# angularclock.net
KiCad netlist of a schematic drawn in EAGLE
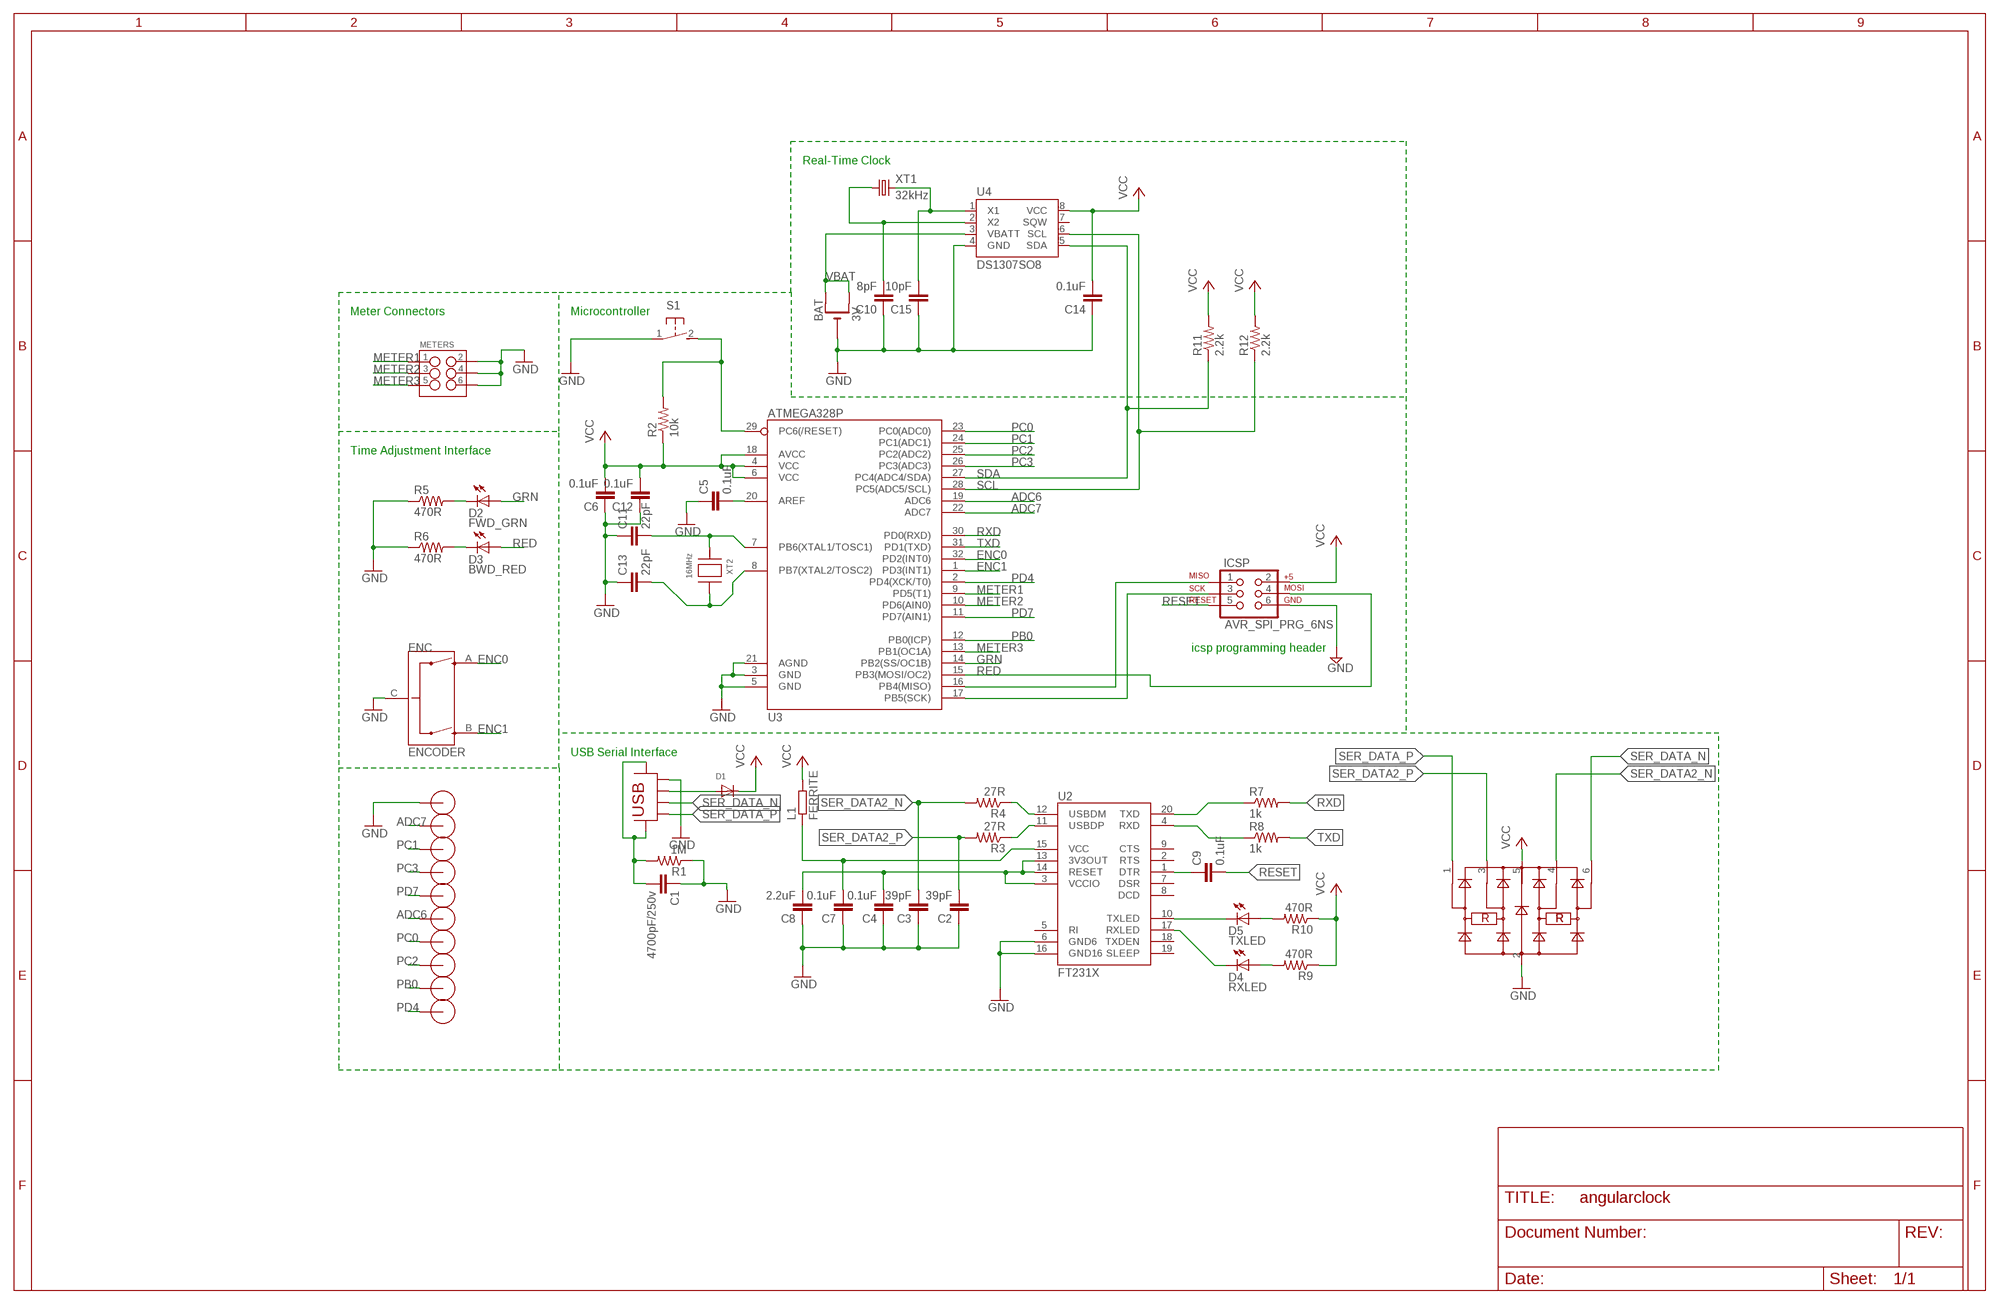
[diagram p0: schematic, sheet 1]

(export (version "E")
  (design (tool "Eeschema 10.0.6"))
  (components
    (comp (ref "BAT")
      (value "3V")
      (footprint "eagle-import:CR1220-THM")
      (libsource (lib "eagle-import") (part "CR1220THM"))
    )
    (comp (ref "C1")
      (value "4700pF/250v")
      (footprint "eagle-import:0805")
      (libsource (lib "eagle-import") (part "CAP0805"))
    )
    (comp (ref "C2")
      (value "39pF")
      (footprint "eagle-import:0805")
      (libsource (lib "eagle-import") (part "CAP0805"))
    )
    (comp (ref "C3")
      (value "39pF")
      (footprint "eagle-import:0805")
      (libsource (lib "eagle-import") (part "CAP0805"))
    )
    (comp (ref "C4")
      (value "0.1uF")
      (footprint "eagle-import:0805")
      (libsource (lib "eagle-import") (part "CAP0805"))
    )
    (comp (ref "C5")
      (value "0.1uF")
      (footprint "eagle-import:0805")
      (libsource (lib "eagle-import") (part "CAP0805"))
    )
    (comp (ref "C6")
      (value "0.1uF")
      (footprint "eagle-import:0805")
      (libsource (lib "eagle-import") (part "CAP0805"))
    )
    (comp (ref "C7")
      (value "0.1uF")
      (footprint "eagle-import:0805")
      (libsource (lib "eagle-import") (part "CAP0805"))
    )
    (comp (ref "C8")
      (value "2.2uF")
      (footprint "eagle-import:0805")
      (libsource (lib "eagle-import") (part "CAP0805"))
    )
    (comp (ref "C9")
      (value "0.1uF")
      (footprint "eagle-import:0805")
      (libsource (lib "eagle-import") (part "CAP0805"))
    )
    (comp (ref "C10")
      (value "8pF")
      (footprint "eagle-import:0805")
      (libsource (lib "eagle-import") (part "CAP0805"))
    )
    (comp (ref "C11")
      (value "22pF")
      (footprint "eagle-import:0805")
      (libsource (lib "eagle-import") (part "CAP0805"))
    )
    (comp (ref "C12")
      (value "0.1uF")
      (footprint "eagle-import:0805")
      (libsource (lib "eagle-import") (part "CAP0805"))
    )
    (comp (ref "C13")
      (value "22pF")
      (footprint "eagle-import:0805")
      (libsource (lib "eagle-import") (part "CAP0805"))
    )
    (comp (ref "C14")
      (value "0.1uF")
      (footprint "eagle-import:0805")
      (libsource (lib "eagle-import") (part "CAP0805"))
    )
    (comp (ref "C15")
      (value "10pF")
      (footprint "eagle-import:0805")
      (libsource (lib "eagle-import") (part "CAP0805"))
    )
    (comp (ref "D1")
      (value "MBRM130LT1G")
      (footprint "eagle-import:DO-216AA")
      (libsource (lib "eagle-import") (part "MBRM130LT1G"))
    )
    (comp (ref "D2")
      (value "FWD_GRN")
      (footprint "eagle-import:CHIPLED_0805")
      (libsource (lib "eagle-import") (part "LEDCHIPLED_0805"))
    )
    (comp (ref "D3")
      (value "BWD_RED")
      (footprint "eagle-import:CHIPLED_0805")
      (libsource (lib "eagle-import") (part "LEDCHIPLED_0805"))
    )
    (comp (ref "D4")
      (value "RXLED")
      (footprint "eagle-import:CHIPLED_0805")
      (libsource (lib "eagle-import") (part "LEDCHIPLED_0805"))
    )
    (comp (ref "D5")
      (value "TXLED")
      (footprint "eagle-import:CHIPLED_0805")
      (libsource (lib "eagle-import") (part "LEDCHIPLED_0805"))
    )
    (comp (ref "ENC")
      (value "ENCODER")
      (footprint "eagle-import:ENCODER-16MM-QUAD")
      (libsource (lib "eagle-import") (part "ENCODER-QUADRATURE"))
    )
    (comp (ref "ICSP")
      (value "AVR_SPI_PRG_6NS")
      (footprint "eagle-import:2X3-NS")
      (libsource (lib "eagle-import") (part "AVR_SPI_PRG_6NS"))
    )
    (comp (ref "L1")
      (value "FERRITE")
      (footprint "eagle-import:R0805")
      (libsource (lib "eagle-import") (part "R-EU_R0805"))
    )
    (comp (ref "METERS")
      (value "M03X2NO_SILK")
      (footprint "eagle-import:2X3-NS")
      (libsource (lib "eagle-import") (part "M03X2NO_SILK"))
    )
    (comp (ref "R1")
      (value "1M")
      (footprint "eagle-import:0805")
      (libsource (lib "eagle-import") (part "RESISTOR0805-RES"))
    )
    (comp (ref "R2")
      (value "10k")
      (footprint "eagle-import:0805")
      (libsource (lib "eagle-import") (part "RESISTOR0805-RES"))
    )
    (comp (ref "R3")
      (value "27R")
      (footprint "eagle-import:0805")
      (libsource (lib "eagle-import") (part "RESISTOR0805-RES"))
    )
    (comp (ref "R4")
      (value "27R")
      (footprint "eagle-import:0805")
      (libsource (lib "eagle-import") (part "RESISTOR0805-RES"))
    )
    (comp (ref "R5")
      (value "470R")
      (footprint "eagle-import:0805")
      (libsource (lib "eagle-import") (part "RESISTOR0805-RES"))
    )
    (comp (ref "R6")
      (value "470R")
      (footprint "eagle-import:0805")
      (libsource (lib "eagle-import") (part "RESISTOR0805-RES"))
    )
    (comp (ref "R7")
      (value "1k")
      (footprint "eagle-import:0805")
      (libsource (lib "eagle-import") (part "RESISTOR0805-RES"))
    )
    (comp (ref "R8")
      (value "1k")
      (footprint "eagle-import:0805")
      (libsource (lib "eagle-import") (part "RESISTOR0805-RES"))
    )
    (comp (ref "R9")
      (value "470R")
      (footprint "eagle-import:0805")
      (libsource (lib "eagle-import") (part "RESISTOR0805-RES"))
    )
    (comp (ref "R10")
      (value "470R")
      (footprint "eagle-import:0805")
      (libsource (lib "eagle-import") (part "RESISTOR0805-RES"))
    )
    (comp (ref "R11")
      (value "2.2k")
      (footprint "eagle-import:0805")
      (libsource (lib "eagle-import") (part "RESISTOR0805-RES"))
    )
    (comp (ref "R12")
      (value "2.2k")
      (footprint "eagle-import:0805")
      (libsource (lib "eagle-import") (part "RESISTOR0805-RES"))
    )
    (comp (ref "S1")
      (value "31-XX")
      (footprint "eagle-import:B3F-31XX")
      (libsource (lib "eagle-import") (part "31-XX"))
    )
    (comp (ref "U$1")
      (value "1PIN")
      (footprint "eagle-import:1PIN")
      (libsource (lib "eagle-import") (part "1PIN"))
    )
    (comp (ref "U$2")
      (value "1PIN")
      (footprint "eagle-import:1PIN")
      (libsource (lib "eagle-import") (part "1PIN"))
    )
    (comp (ref "U$3")
      (value "1PIN")
      (footprint "eagle-import:1PIN")
      (libsource (lib "eagle-import") (part "1PIN"))
    )
    (comp (ref "U$4")
      (value "1PIN")
      (footprint "eagle-import:1PIN")
      (libsource (lib "eagle-import") (part "1PIN"))
    )
    (comp (ref "U$5")
      (value "1PIN")
      (footprint "eagle-import:1PIN")
      (libsource (lib "eagle-import") (part "1PIN"))
    )
    (comp (ref "U$6")
      (value "1PIN")
      (footprint "eagle-import:1PIN")
      (libsource (lib "eagle-import") (part "1PIN"))
    )
    (comp (ref "U$7")
      (value "1PIN")
      (footprint "eagle-import:1PIN")
      (libsource (lib "eagle-import") (part "1PIN"))
    )
    (comp (ref "U$8")
      (value "1PIN")
      (footprint "eagle-import:1PIN")
      (libsource (lib "eagle-import") (part "1PIN"))
    )
    (comp (ref "U$9")
      (value "1PIN")
      (footprint "eagle-import:1PIN")
      (libsource (lib "eagle-import") (part "1PIN"))
    )
    (comp (ref "U$10")
      (value "1PIN")
      (footprint "eagle-import:1PIN")
      (libsource (lib "eagle-import") (part "1PIN"))
    )
    (comp (ref "U1")
      (value "IP4234CZ6")
      (footprint "eagle-import:SOT457")
      (libsource (lib "eagle-import") (part "IP4234CZ6"))
    )
    (comp (ref "U2")
      (value "FT231X")
      (footprint "eagle-import:SSOP20")
      (libsource (lib "eagle-import") (part "FT231X"))
    )
    (comp (ref "U3")
      (value "ATMEGA328P")
      (footprint "eagle-import:TQFP32-08")
      (libsource (lib "eagle-import") (part "ATMEGA328_SMT"))
    )
    (comp (ref "U4")
      (value "DS1307SO8")
      (footprint "eagle-import:SO08")
      (libsource (lib "eagle-import") (part "DS1307SO8"))
    )
    (comp (ref "USB")
      (value "MICRO-USB-POWERMICRO-USB-2-ROUND-HOLES")
      (footprint "eagle-import:WICKED-DEVICE_MICRO-USB-4")
      (libsource (lib "eagle-import") (part "WICKED-DEVICE_MICRO-USB-POWERMICRO-USB-4"))
    )
    (comp (ref "XT1")
      (value "32kHz")
      (footprint "eagle-import:CRYSTAL_TC26V")
      (libsource (lib "eagle-import") (part "CRYSTAL_CRYSTALTC26V"))
    )
    (comp (ref "XT2")
      (value "16MHz")
      (footprint "eagle-import:ABLS")
      (libsource (lib "eagle-import") (part "ABLS"))
    )
  )
  (nets
    (net (code "1") (name "/ADC6") (class "Default")
      (node (ref "U$1") (pin "1") (pinfunction "1_1") (pintype "bidirectional"))
      (node (ref "U3") (pin "19") (pinfunction "ADC6_19") (pintype "bidirectional"))
    )
    (net (code "2") (name "/ADC7") (class "Default")
      (node (ref "U$4") (pin "1") (pinfunction "1_1") (pintype "bidirectional"))
      (node (ref "U3") (pin "22") (pinfunction "ADC7_22") (pintype "bidirectional"))
    )
    (net (code "3") (name "/ENC0") (class "Default")
      (node (ref "ENC") (pin "A") (pinfunction "A_A") (pintype "bidirectional"))
      (node (ref "U3") (pin "32") (pinfunction "PD2(INT0)_32") (pintype "bidirectional"))
    )
    (net (code "4") (name "/ENC1") (class "Default")
      (node (ref "ENC") (pin "B") (pinfunction "B_B") (pintype "bidirectional"))
      (node (ref "U3") (pin "1") (pinfunction "PD3(INT1)_1") (pintype "bidirectional"))
    )
    (net (code "5") (name "/GRN") (class "Default")
      (node (ref "D2") (pin "A") (pinfunction "A_A") (pintype "passive"))
      (node (ref "U3") (pin "14") (pinfunction "PB2(SS/OC1B)_14") (pintype "bidirectional"))
    )
    (net (code "6") (name "/METER1") (class "Default")
      (node (ref "METERS") (pin "1") (pinfunction "1_1") (pintype "bidirectional"))
      (node (ref "U3") (pin "9") (pinfunction "PD5(T1)_9") (pintype "bidirectional"))
    )
    (net (code "7") (name "/METER2") (class "Default")
      (node (ref "METERS") (pin "3") (pinfunction "3_3") (pintype "bidirectional"))
      (node (ref "U3") (pin "10") (pinfunction "PD6(AIN0)_10") (pintype "bidirectional"))
    )
    (net (code "8") (name "/METER3") (class "Default")
      (node (ref "METERS") (pin "5") (pinfunction "5_5") (pintype "bidirectional"))
      (node (ref "U3") (pin "13") (pinfunction "PB1(OC1A)_13") (pintype "bidirectional"))
    )
    (net (code "9") (name "/PB0") (class "Default")
      (node (ref "U$5") (pin "1") (pinfunction "1_1") (pintype "bidirectional"))
      (node (ref "U3") (pin "12") (pinfunction "PB0(ICP)_12") (pintype "bidirectional"))
    )
    (net (code "10") (name "/PC0") (class "Default")
      (node (ref "U$3") (pin "1") (pinfunction "1_1") (pintype "bidirectional"))
      (node (ref "U3") (pin "23") (pinfunction "PC0(ADC0)_23") (pintype "bidirectional"))
    )
    (net (code "11") (name "/PC1") (class "Default")
      (node (ref "U$6") (pin "1") (pinfunction "1_1") (pintype "bidirectional"))
      (node (ref "U3") (pin "24") (pinfunction "PC1(ADC1)_24") (pintype "bidirectional"))
    )
    (net (code "12") (name "/PC2") (class "Default")
      (node (ref "U$7") (pin "1") (pinfunction "1_1") (pintype "bidirectional"))
      (node (ref "U3") (pin "25") (pinfunction "PC2(ADC2)_25") (pintype "bidirectional"))
    )
    (net (code "13") (name "/PC3") (class "Default")
      (node (ref "U$10") (pin "1") (pinfunction "1_1") (pintype "bidirectional"))
      (node (ref "U3") (pin "26") (pinfunction "PC3(ADC3)_26") (pintype "bidirectional"))
    )
    (net (code "14") (name "/PD4") (class "Default")
      (node (ref "U$9") (pin "1") (pinfunction "1_1") (pintype "bidirectional"))
      (node (ref "U3") (pin "2") (pinfunction "PD4(XCK/T0)_2") (pintype "bidirectional"))
    )
    (net (code "15") (name "/PD7") (class "Default")
      (node (ref "U$8") (pin "1") (pinfunction "1_1") (pintype "bidirectional"))
      (node (ref "U3") (pin "11") (pinfunction "PD7(AIN1)_11") (pintype "bidirectional"))
    )
    (net (code "16") (name "/RED") (class "Default")
      (node (ref "D3") (pin "A") (pinfunction "A_A") (pintype "passive"))
      (node (ref "ICSP") (pin "4") (pinfunction "4_4") (pintype "passive"))
      (node (ref "U3") (pin "15") (pinfunction "PB3(MOSI/OC2)_15") (pintype "bidirectional"))
    )
    (net (code "17") (name "/SCL") (class "Default")
      (node (ref "R12") (pin "1") (pinfunction "1_1") (pintype "passive"))
      (node (ref "U3") (pin "28") (pinfunction "PC5(ADC5/SCL)_28") (pintype "bidirectional"))
      (node (ref "U4") (pin "6") (pinfunction "SCL_6") (pintype "bidirectional"))
    )
    (net (code "18") (name "/SDA") (class "Default")
      (node (ref "R11") (pin "1") (pinfunction "1_1") (pintype "passive"))
      (node (ref "U3") (pin "27") (pinfunction "PC4(ADC4/SDA)_27") (pintype "bidirectional"))
      (node (ref "U4") (pin "5") (pinfunction "SDA_5") (pintype "bidirectional"))
    )
    (net (code "19") (name "/VBAT") (class "Default")
      (node (ref "BAT") (pin "+1") (pinfunction "+_+1") (pintype "passive"))
      (node (ref "BAT") (pin "+2") (pinfunction "+1_+2") (pintype "passive"))
      (node (ref "U4") (pin "3") (pinfunction "VBATT_3") (pintype "bidirectional"))
    )
    (net (code "20") (name "GND") (class "Default")
      (node (ref "BAT") (pin "-") (pinfunction "-_-") (pintype "passive"))
      (node (ref "C1") (pin "1") (pinfunction "1_1") (pintype "passive"))
      (node (ref "C10") (pin "1") (pinfunction "1_1") (pintype "passive"))
      (node (ref "C11") (pin "1") (pinfunction "1_1") (pintype "passive"))
      (node (ref "C12") (pin "1") (pinfunction "1_1") (pintype "passive"))
      (node (ref "C13") (pin "1") (pinfunction "1_1") (pintype "passive"))
      (node (ref "C14") (pin "1") (pinfunction "1_1") (pintype "passive"))
      (node (ref "C15") (pin "1") (pinfunction "1_1") (pintype "passive"))
      (node (ref "C2") (pin "1") (pinfunction "1_1") (pintype "passive"))
      (node (ref "C3") (pin "1") (pinfunction "1_1") (pintype "passive"))
      (node (ref "C4") (pin "1") (pinfunction "1_1") (pintype "passive"))
      (node (ref "C5") (pin "1") (pinfunction "1_1") (pintype "passive"))
      (node (ref "C6") (pin "1") (pinfunction "1_1") (pintype "passive"))
      (node (ref "C7") (pin "1") (pinfunction "1_1") (pintype "passive"))
      (node (ref "C8") (pin "1") (pinfunction "1_1") (pintype "passive"))
      (node (ref "ENC") (pin "C") (pinfunction "C_C") (pintype "bidirectional"))
      (node (ref "ICSP") (pin "6") (pinfunction "6_6") (pintype "passive"))
      (node (ref "METERS") (pin "2") (pinfunction "2_2") (pintype "bidirectional"))
      (node (ref "METERS") (pin "4") (pinfunction "4_4") (pintype "bidirectional"))
      (node (ref "METERS") (pin "6") (pinfunction "6_6") (pintype "bidirectional"))
      (node (ref "R1") (pin "1") (pinfunction "1_1") (pintype "passive"))
      (node (ref "R5") (pin "1") (pinfunction "1_1") (pintype "passive"))
      (node (ref "R6") (pin "1") (pinfunction "1_1") (pintype "passive"))
      (node (ref "S1") (pin "1") (pinfunction "P_1") (pintype "passive"))
      (node (ref "U$2") (pin "1") (pinfunction "1_1") (pintype "bidirectional"))
      (node (ref "U1") (pin "2") (pinfunction "2_2") (pintype "bidirectional"))
      (node (ref "U2") (pin "16") (pinfunction "GND16_16") (pintype "power_in"))
      (node (ref "U2") (pin "6") (pinfunction "GND6_6") (pintype "power_in"))
      (node (ref "U3") (pin "21") (pinfunction "AGND_21") (pintype "bidirectional"))
      (node (ref "U3") (pin "3") (pinfunction "GND_3") (pintype "bidirectional"))
      (node (ref "U3") (pin "5") (pinfunction "GND_5") (pintype "bidirectional"))
      (node (ref "U4") (pin "4") (pinfunction "GND_4") (pintype "bidirectional"))
      (node (ref "USB") (pin "GND") (pinfunction "GND_GND") (pintype "power_in"))
    )
    (net (code "21") (name "Net-(D1-Pad+)") (class "Default")
      (node (ref "D1") (pin "+") (pinfunction "+_+") (pintype "passive"))
      (node (ref "USB") (pin "VBUS") (pinfunction "VBUS_VBUS") (pintype "power_in"))
    )
    (net (code "22") (name "Net-(D2-PadC)") (class "Default")
      (node (ref "D2") (pin "C") (pinfunction "C_C") (pintype "passive"))
      (node (ref "R5") (pin "2") (pinfunction "2_2") (pintype "passive"))
    )
    (net (code "23") (name "Net-(D3-PadC)") (class "Default")
      (node (ref "D3") (pin "C") (pinfunction "C_C") (pintype "passive"))
      (node (ref "R6") (pin "2") (pinfunction "2_2") (pintype "passive"))
    )
    (net (code "24") (name "Net-(D4-PadA)") (class "Default")
      (node (ref "D4") (pin "A") (pinfunction "A_A") (pintype "passive"))
      (node (ref "R9") (pin "2") (pinfunction "2_2") (pintype "passive"))
    )
    (net (code "25") (name "Net-(D5-PadA)") (class "Default")
      (node (ref "D5") (pin "A") (pinfunction "A_A") (pintype "passive"))
      (node (ref "R10") (pin "2") (pinfunction "2_2") (pintype "passive"))
    )
    (net (code "26") (name "Net-(U2-3V3OUT)") (class "Default")
      (node (ref "C4") (pin "2") (pinfunction "2_2") (pintype "passive"))
      (node (ref "C8") (pin "2") (pinfunction "2_2") (pintype "passive"))
      (node (ref "U2") (pin "13") (pinfunction "3V3OUT_13") (pintype "output"))
      (node (ref "U2") (pin "14") (pinfunction "RESET_14") (pintype "input"))
      (node (ref "U2") (pin "3") (pinfunction "VCCIO_3") (pintype "power_in"))
    )
    (net (code "27") (name "Net-(U2-DTR)") (class "Default")
      (node (ref "C9") (pin "1") (pinfunction "1_1") (pintype "passive"))
      (node (ref "U2") (pin "1") (pinfunction "DTR_1") (pintype "output"))
    )
    (net (code "28") (name "Net-(U2-RXD)") (class "Default")
      (node (ref "R8") (pin "1") (pinfunction "1_1") (pintype "passive"))
      (node (ref "U2") (pin "4") (pinfunction "RXD_4") (pintype "input"))
    )
    (net (code "29") (name "Net-(U2-RXLED)") (class "Default")
      (node (ref "D4") (pin "C") (pinfunction "C_C") (pintype "passive"))
      (node (ref "U2") (pin "17") (pinfunction "RXLED_17") (pintype "input"))
    )
    (net (code "30") (name "Net-(U2-TXD)") (class "Default")
      (node (ref "R7") (pin "1") (pinfunction "1_1") (pintype "passive"))
      (node (ref "U2") (pin "20") (pinfunction "TXD_20") (pintype "output"))
    )
    (net (code "31") (name "Net-(U2-TXLED)") (class "Default")
      (node (ref "D5") (pin "C") (pinfunction "C_C") (pintype "passive"))
      (node (ref "U2") (pin "10") (pinfunction "TXLED_10") (pintype "input"))
    )
    (net (code "32") (name "Net-(U2-USBDM)") (class "Default")
      (node (ref "R4") (pin "1") (pinfunction "1_1") (pintype "passive"))
      (node (ref "U2") (pin "12") (pinfunction "USBDM_12") (pintype "bidirectional"))
    )
    (net (code "33") (name "Net-(U2-USBDP)") (class "Default")
      (node (ref "R3") (pin "1") (pinfunction "1_1") (pintype "passive"))
      (node (ref "U2") (pin "11") (pinfunction "USBDP_11") (pintype "bidirectional"))
    )
    (net (code "34") (name "Net-(U2-VCC)") (class "Default")
      (node (ref "C7") (pin "2") (pinfunction "2_2") (pintype "passive"))
      (node (ref "L1") (pin "1") (pinfunction "1_1") (pintype "passive"))
      (node (ref "U2") (pin "15") (pinfunction "VCC_15") (pintype "power_in"))
    )
    (net (code "35") (name "Net-(U3-AREF)") (class "Default")
      (node (ref "C5") (pin "2") (pinfunction "2_2") (pintype "passive"))
      (node (ref "U3") (pin "20") (pinfunction "AREF_20") (pintype "bidirectional"))
    )
    (net (code "36") (name "Net-(U3-PB4(MISO))") (class "Default")
      (node (ref "ICSP") (pin "1") (pinfunction "1_1") (pintype "passive"))
      (node (ref "U3") (pin "16") (pinfunction "PB4(MISO)_16") (pintype "bidirectional"))
    )
    (net (code "37") (name "Net-(U3-PB5(SCK))") (class "Default")
      (node (ref "ICSP") (pin "3") (pinfunction "3_3") (pintype "passive"))
      (node (ref "U3") (pin "17") (pinfunction "PB5(SCK)_17") (pintype "bidirectional"))
    )
    (net (code "38") (name "Net-(U3-PB6(XTAL1{slash}TOSC1))") (class "Default")
      (node (ref "C11") (pin "2") (pinfunction "2_2") (pintype "passive"))
      (node (ref "U3") (pin "7") (pinfunction "PB6(XTAL1/TOSC1)_7") (pintype "bidirectional"))
      (node (ref "XT2") (pin "1") (pinfunction "P$1_1") (pintype "bidirectional"))
    )
    (net (code "39") (name "Net-(U3-PB7(XTAL2{slash}TOSC2))") (class "Default")
      (node (ref "C13") (pin "2") (pinfunction "2_2") (pintype "passive"))
      (node (ref "U3") (pin "8") (pinfunction "PB7(XTAL2/TOSC2)_8") (pintype "bidirectional"))
      (node (ref "XT2") (pin "2") (pinfunction "P$2_2") (pintype "bidirectional"))
    )
    (net (code "40") (name "Net-(U4-X1)") (class "Default")
      (node (ref "C15") (pin "2") (pinfunction "2_2") (pintype "passive"))
      (node (ref "U4") (pin "1") (pinfunction "X1_1") (pintype "bidirectional"))
      (node (ref "XT1") (pin "2") (pinfunction "2_2") (pintype "passive"))
    )
    (net (code "41") (name "Net-(U4-X2)") (class "Default")
      (node (ref "C10") (pin "2") (pinfunction "2_2") (pintype "passive"))
      (node (ref "U4") (pin "2") (pinfunction "X2_2") (pintype "bidirectional"))
      (node (ref "XT1") (pin "1") (pinfunction "1_1") (pintype "passive"))
    )
    (net (code "42") (name "Net-(USB-P$1)") (class "Default")
      (node (ref "C1") (pin "2") (pinfunction "2_2") (pintype "passive"))
      (node (ref "R1") (pin "2") (pinfunction "2_2") (pintype "passive"))
      (node (ref "USB") (pin "P$2") (pinfunction "P$1_P$2") (pintype "bidirectional"))
      (node (ref "USB") (pin "P$3") (pinfunction "P$2_P$3") (pintype "bidirectional"))
    )
    (net (code "43") (name "RESET") (class "Default")
      (node (ref "C9") (pin "2") (pinfunction "2_2") (pintype "passive"))
      (node (ref "ICSP") (pin "5") (pinfunction "5_5") (pintype "passive"))
      (node (ref "R2") (pin "2") (pinfunction "2_2") (pintype "passive"))
      (node (ref "S1") (pin "2") (pinfunction "S_2") (pintype "passive"))
      (node (ref "U3") (pin "29") (pinfunction "PC6(/RESET)_29") (pintype "bidirectional"))
    )
    (net (code "44") (name "RXD") (class "Default")
      (node (ref "R7") (pin "2") (pinfunction "2_2") (pintype "passive"))
      (node (ref "U3") (pin "30") (pinfunction "PD0(RXD)_30") (pintype "bidirectional"))
    )
    (net (code "45") (name "SER_DATA2_N") (class "Default")
      (node (ref "C3") (pin "2") (pinfunction "2_2") (pintype "passive"))
      (node (ref "R4") (pin "2") (pinfunction "2_2") (pintype "passive"))
      (node (ref "U1") (pin "4") (pinfunction "6_4") (pintype "bidirectional"))
    )
    (net (code "46") (name "SER_DATA2_P") (class "Default")
      (node (ref "C2") (pin "2") (pinfunction "2_2") (pintype "passive"))
      (node (ref "R3") (pin "2") (pinfunction "2_2") (pintype "passive"))
      (node (ref "U1") (pin "3") (pinfunction "3_3") (pintype "bidirectional"))
    )
    (net (code "47") (name "SER_DATA_N") (class "Default")
      (node (ref "U1") (pin "6") (pinfunction "4_6") (pintype "bidirectional"))
      (node (ref "USB") (pin "D-") (pinfunction "D-_D-") (pintype "bidirectional"))
    )
    (net (code "48") (name "SER_DATA_P") (class "Default")
      (node (ref "U1") (pin "1") (pinfunction "1_1") (pintype "bidirectional"))
      (node (ref "USB") (pin "D+") (pinfunction "D+_D+") (pintype "bidirectional"))
    )
    (net (code "49") (name "TXD") (class "Default")
      (node (ref "R8") (pin "2") (pinfunction "2_2") (pintype "passive"))
      (node (ref "U3") (pin "31") (pinfunction "PD1(TXD)_31") (pintype "bidirectional"))
    )
    (net (code "50") (name "VCC") (class "Default")
      (node (ref "C12") (pin "2") (pinfunction "2_2") (pintype "passive"))
      (node (ref "C14") (pin "2") (pinfunction "2_2") (pintype "passive"))
      (node (ref "C6") (pin "2") (pinfunction "2_2") (pintype "passive"))
      (node (ref "D1") (pin "-") (pinfunction "-_-") (pintype "passive"))
      (node (ref "ICSP") (pin "2") (pinfunction "2_2") (pintype "passive"))
      (node (ref "L1") (pin "2") (pinfunction "2_2") (pintype "passive"))
      (node (ref "R10") (pin "1") (pinfunction "1_1") (pintype "passive"))
      (node (ref "R11") (pin "2") (pinfunction "2_2") (pintype "passive"))
      (node (ref "R12") (pin "2") (pinfunction "2_2") (pintype "passive"))
      (node (ref "R2") (pin "1") (pinfunction "1_1") (pintype "passive"))
      (node (ref "R9") (pin "1") (pinfunction "1_1") (pintype "passive"))
      (node (ref "U1") (pin "5") (pinfunction "5_5") (pintype "bidirectional"))
      (node (ref "U3") (pin "18") (pinfunction "AVCC_18") (pintype "bidirectional"))
      (node (ref "U3") (pin "4") (pinfunction "VCC_4") (pintype "bidirectional"))
      (node (ref "U3") (pin "6") (pinfunction "VCC_6") (pintype "bidirectional"))
      (node (ref "U4") (pin "8") (pinfunction "VCC_8") (pintype "bidirectional"))
    )
    (net (code "51") (name "unconnected-(U2-CTS-Pad9)") (class "Default")
      (node (ref "U2") (pin "9") (pinfunction "CTS_9") (pintype "input"))
    )
    (net (code "52") (name "unconnected-(U2-DCD-Pad8)") (class "Default")
      (node (ref "U2") (pin "8") (pinfunction "DCD_8") (pintype "input"))
    )
    (net (code "53") (name "unconnected-(U2-DSR-Pad7)") (class "Default")
      (node (ref "U2") (pin "7") (pinfunction "DSR_7") (pintype "input"))
    )
    (net (code "54") (name "unconnected-(U2-RI-Pad5)") (class "Default")
      (node (ref "U2") (pin "5") (pinfunction "RI_5") (pintype "input"))
    )
    (net (code "55") (name "unconnected-(U2-RTS-Pad2)") (class "Default")
      (node (ref "U2") (pin "2") (pinfunction "RTS_2") (pintype "output"))
    )
    (net (code "56") (name "unconnected-(U2-SLEEP-Pad19)") (class "Default")
      (node (ref "U2") (pin "19") (pinfunction "SLEEP_19") (pintype "input"))
    )
    (net (code "57") (name "unconnected-(U2-TXDEN-Pad18)") (class "Default")
      (node (ref "U2") (pin "18") (pinfunction "TXDEN_18") (pintype "input"))
    )
    (net (code "58") (name "unconnected-(U4-SQW-Pad7)") (class "Default")
      (node (ref "U4") (pin "7") (pinfunction "SQW_7") (pintype "bidirectional"))
    )
  )
)
